# Radial-V_Ext.net
KiCad netlist of a schematic drawn in EAGLE
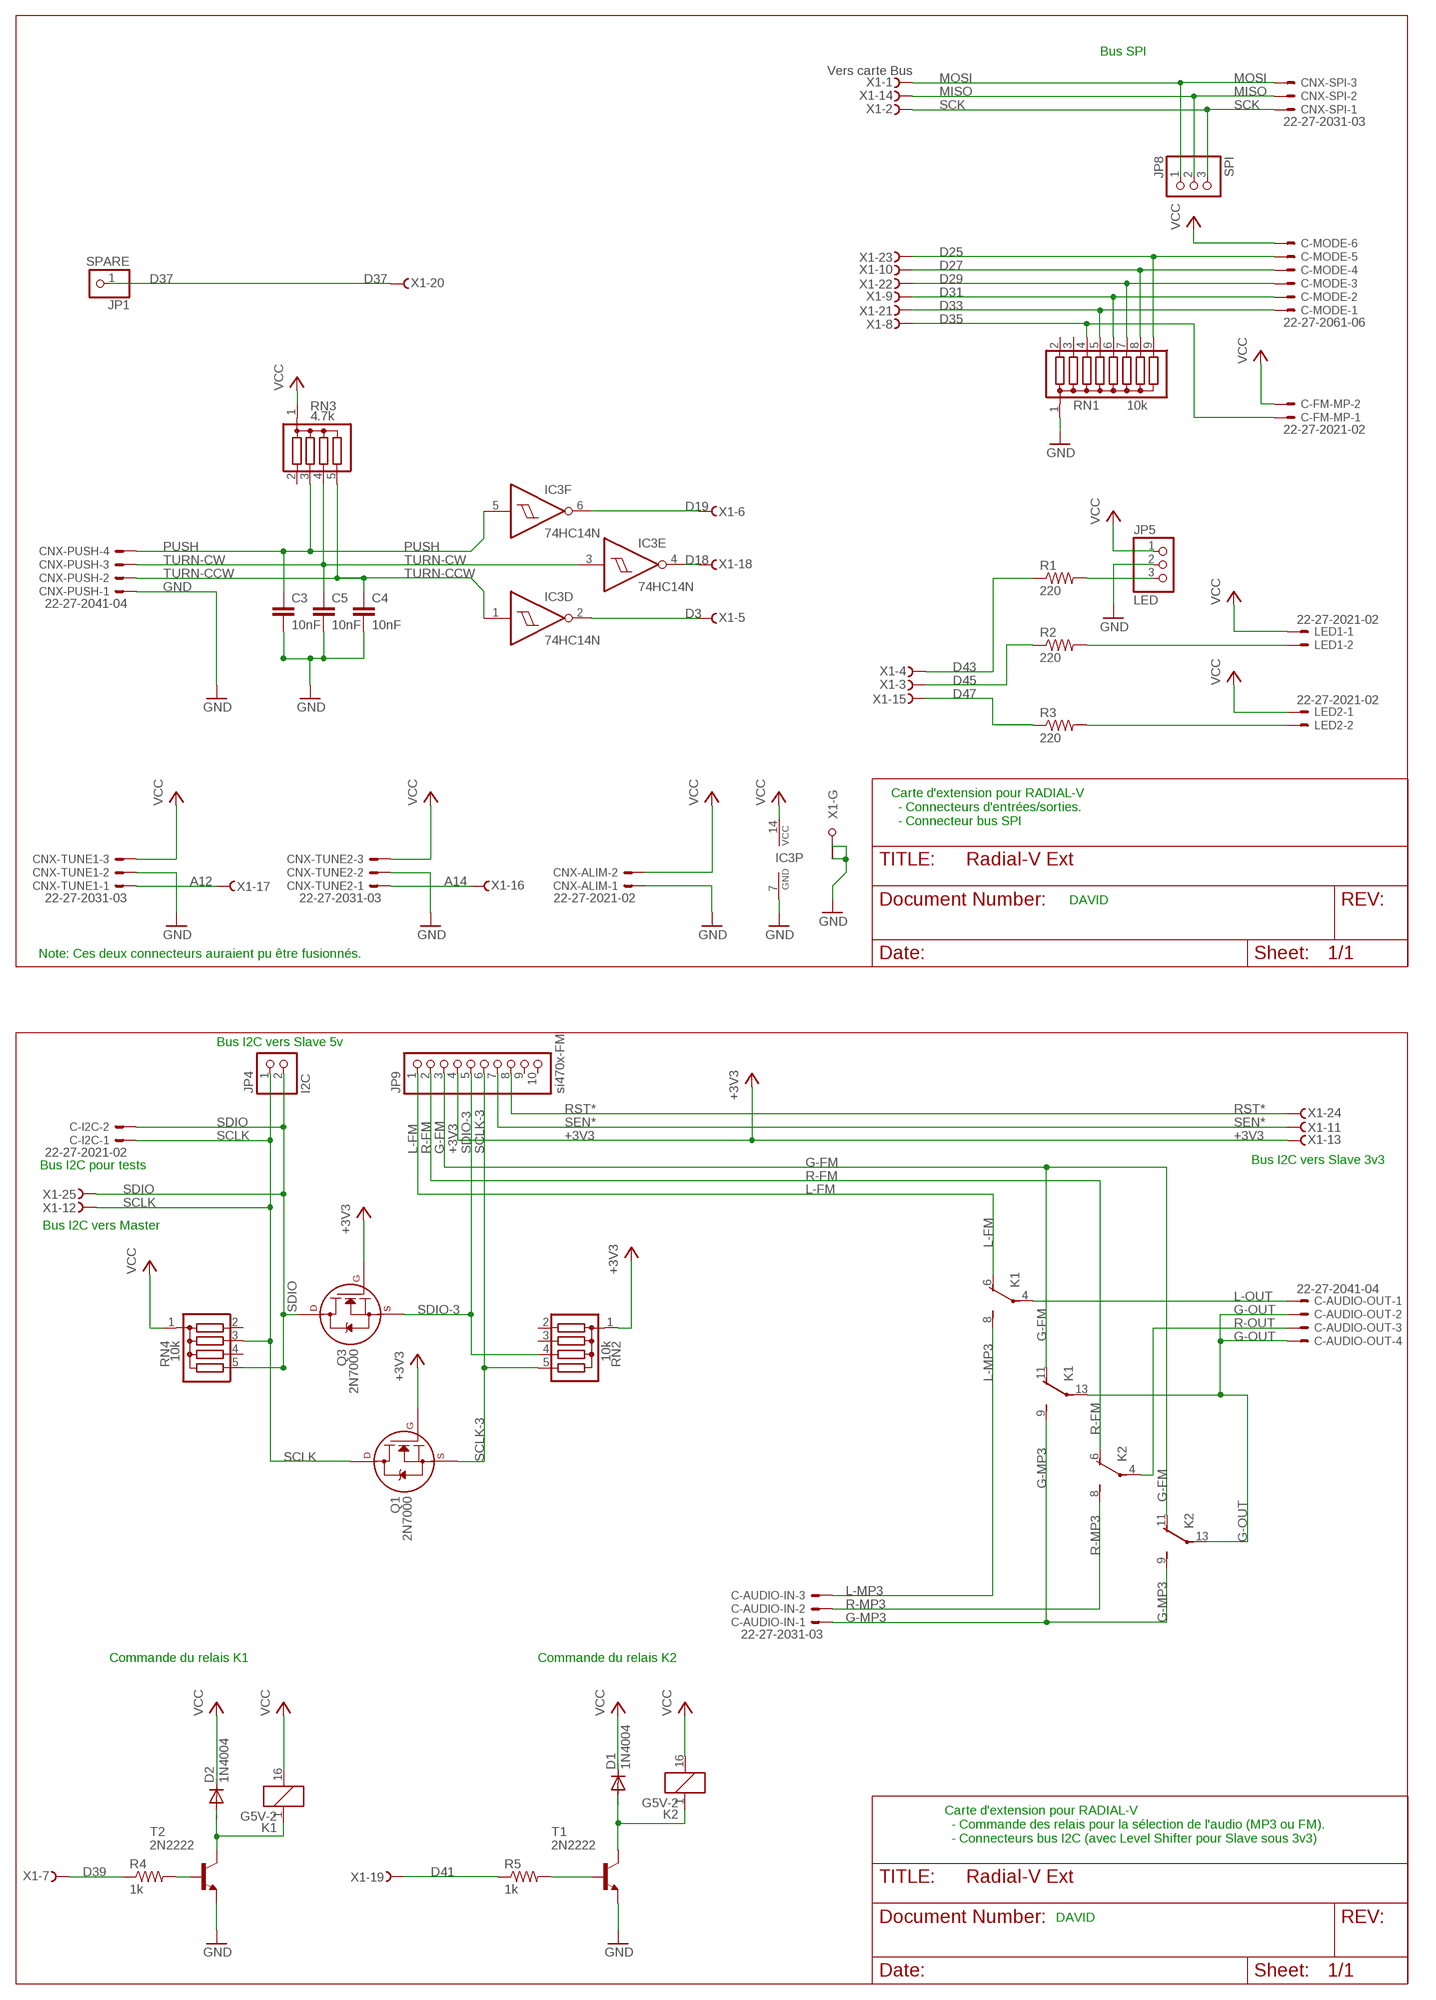
[diagram p0: schematic, sheet 1]

(export (version "E")
  (design (tool "Eeschema 10.0.6"))
  (components
    (comp (ref "C-AUDIO-IN")
      (value "22-27-2031-03")
      (footprint "eagle-import:6410-03")
      (fields (field (name "OC_FARNELL") "2366181"))
      (libsource (lib "eagle-import") (part "22-?-0327-2031"))
    )
    (comp (ref "C-AUDIO-OUT")
      (value "22-27-2041-04")
      (footprint "eagle-import:6410-04")
      (libsource (lib "eagle-import") (part "22-?-0427-2041"))
    )
    (comp (ref "C-FM-MP")
      (value "22-27-2021-02")
      (footprint "eagle-import:6410-02")
      (libsource (lib "eagle-import") (part "22-?-0227-2021"))
    )
    (comp (ref "C-I2C")
      (value "22-27-2021-02")
      (footprint "eagle-import:6410-02")
      (libsource (lib "eagle-import") (part "22-?-0227-2021"))
    )
    (comp (ref "C-MODE")
      (value "22-27-2061-06")
      (footprint "eagle-import:6410-06")
      (libsource (lib "eagle-import") (part "22-?-0627-2061"))
    )
    (comp (ref "C3")
      (value "10nF")
      (footprint "eagle-import:C050-050X075")
      (libsource (lib "eagle-import") (part "C-EU050-050X075"))
    )
    (comp (ref "C4")
      (value "10nF")
      (footprint "eagle-import:C050-050X075")
      (libsource (lib "eagle-import") (part "C-EU050-050X075"))
    )
    (comp (ref "C5")
      (value "10nF")
      (footprint "eagle-import:C050-050X075")
      (libsource (lib "eagle-import") (part "C-EU050-050X075"))
    )
    (comp (ref "CNX-ALIM")
      (value "22-27-2021-02")
      (footprint "eagle-import:6410-02")
      (libsource (lib "eagle-import") (part "22-?-0227-2021"))
    )
    (comp (ref "CNX-PUSH")
      (value "22-27-2041-04")
      (footprint "eagle-import:6410-04")
      (libsource (lib "eagle-import") (part "22-?-0427-2041"))
    )
    (comp (ref "CNX-SPI")
      (value "22-27-2031-03")
      (footprint "eagle-import:6410-03")
      (libsource (lib "eagle-import") (part "22-?-0327-2031"))
    )
    (comp (ref "CNX-TUNE1")
      (value "22-27-2031-03")
      (footprint "eagle-import:6410-03")
      (fields (field (name "OC_FARNELL") "2366181"))
      (libsource (lib "eagle-import") (part "22-?-0327-2031"))
    )
    (comp (ref "CNX-TUNE2")
      (value "22-27-2031-03")
      (footprint "eagle-import:6410-03")
      (fields (field (name "OC_FARNELL") "2366181"))
      (libsource (lib "eagle-import") (part "22-?-0327-2031"))
    )
    (comp (ref "D1")
      (value "1N4004")
      (footprint "eagle-import:DO41-10")
      (libsource (lib "eagle-import") (part "1N4004"))
    )
    (comp (ref "D2")
      (value "1N4004")
      (footprint "eagle-import:DO41-10")
      (libsource (lib "eagle-import") (part "1N4004"))
    )
    (comp (ref "IC3")
      (value "74HC14N")
      (footprint "eagle-import:DIL14")
      (libsource (lib "eagle-import") (part "7414NHC"))
    )
    (comp (ref "JP1")
      (value "SPARE")
      (footprint "eagle-import:1X01")
      (libsource (lib "eagle-import") (part "PINHD-1X1"))
    )
    (comp (ref "JP4")
      (value "I2C")
      (footprint "eagle-import:1X02")
      (libsource (lib "eagle-import") (part "PINHD-1X2"))
    )
    (comp (ref "JP5")
      (value "LED")
      (footprint "eagle-import:1X03")
      (libsource (lib "eagle-import") (part "PINHD-1X3"))
    )
    (comp (ref "JP8")
      (value "SPI")
      (footprint "eagle-import:1X03")
      (libsource (lib "eagle-import") (part "PINHD-1X3"))
    )
    (comp (ref "JP9")
      (value "si470x-FM")
      (footprint "eagle-import:1X10")
      (libsource (lib "eagle-import") (part "PINHD-1X10"))
    )
    (comp (ref "K1")
      (value "G5V-2")
      (footprint "eagle-import:G5V-2")
      (fields (field (name "MPN") "G5V-2 5DC"))
      (libsource (lib "eagle-import") (part "G5V-2"))
    )
    (comp (ref "K2")
      (value "G5V-2")
      (footprint "eagle-import:G5V-2")
      (fields (field (name "MPN") "G5V-2 5DC"))
      (libsource (lib "eagle-import") (part "G5V-2"))
    )
    (comp (ref "LED1")
      (value "22-27-2021-02")
      (footprint "eagle-import:6410-02")
      (libsource (lib "eagle-import") (part "22-?-0227-2021"))
    )
    (comp (ref "LED2")
      (value "22-27-2021-02")
      (footprint "eagle-import:6410-02")
      (libsource (lib "eagle-import") (part "22-?-0227-2021"))
    )
    (comp (ref "Q1")
      (value "2N7000")
      (footprint "eagle-import:TO-92")
      (libsource (lib "eagle-import") (part "2N700_TO920"))
    )
    (comp (ref "Q3")
      (value "2N7000")
      (footprint "eagle-import:TO-92")
      (libsource (lib "eagle-import") (part "2N700_TO920"))
    )
    (comp (ref "R1")
      (value "220")
      (footprint "eagle-import:0411_15")
      (libsource (lib "eagle-import") (part "R-US_0411/15"))
    )
    (comp (ref "R2")
      (value "220")
      (footprint "eagle-import:0411_15")
      (libsource (lib "eagle-import") (part "R-US_0411/15"))
    )
    (comp (ref "R3")
      (value "220")
      (footprint "eagle-import:0411_15")
      (libsource (lib "eagle-import") (part "R-US_0411/15"))
    )
    (comp (ref "R4")
      (value "1k")
      (footprint "eagle-import:0411_15")
      (libsource (lib "eagle-import") (part "R-US_0411/15"))
    )
    (comp (ref "R5")
      (value "1k")
      (footprint "eagle-import:0411_15")
      (libsource (lib "eagle-import") (part "R-US_0411/15"))
    )
    (comp (ref "RN1")
      (value "10k")
      (footprint "eagle-import:SIL9")
      (libsource (lib "eagle-import") (part "G08R"))
    )
    (comp (ref "RN2")
      (value "10k")
      (footprint "eagle-import:SIL5")
      (libsource (lib "eagle-import") (part "G04R"))
    )
    (comp (ref "RN3")
      (value "4.7k")
      (footprint "eagle-import:SIL5")
      (libsource (lib "eagle-import") (part "G04R"))
    )
    (comp (ref "RN4")
      (value "10k")
      (footprint "eagle-import:SIL5")
      (libsource (lib "eagle-import") (part "G04R"))
    )
    (comp (ref "T1")
      (value "2N2222")
      (footprint "eagle-import:TO18")
      (libsource (lib "eagle-import") (part "2N2222"))
    )
    (comp (ref "T2")
      (value "2N2222")
      (footprint "eagle-import:TO18")
      (libsource (lib "eagle-import") (part "2N2222"))
    )
    (comp (ref "X1")
      (value "Vers carte Bus")
      (footprint "eagle-import:F25HP")
      (libsource (lib "eagle-import") (part "F25HPS"))
    )
  )
  (nets
    (net (code "1") (name "+3V3") (class "Default")
      (node (ref "JP9") (pin "4") (pinfunction "4_4") (pintype "passive"))
      (node (ref "Q1") (pin "2") (pinfunction "G_2") (pintype "tri_state"))
      (node (ref "Q3") (pin "2") (pinfunction "G_2") (pintype "tri_state"))
      (node (ref "RN2") (pin "1") (pinfunction "1_1") (pintype "passive"))
      (node (ref "X1") (pin "13") (pinfunction "F_13") (pintype "passive"))
    )
    (net (code "2") (name "/A12") (class "Default")
      (node (ref "CNX-TUNE1") (pin "1") (pinfunction "S_1") (pintype "passive"))
      (node (ref "X1") (pin "17") (pinfunction "F_17") (pintype "passive"))
    )
    (net (code "3") (name "/A14") (class "Default")
      (node (ref "CNX-TUNE2") (pin "1") (pinfunction "S_1") (pintype "passive"))
      (node (ref "X1") (pin "16") (pinfunction "F_16") (pintype "passive"))
    )
    (net (code "4") (name "/D3") (class "Default")
      (node (ref "IC3") (pin "2") (pinfunction "O_2") (pintype "output"))
      (node (ref "X1") (pin "5") (pinfunction "F_5") (pintype "passive"))
    )
    (net (code "5") (name "/D18") (class "Default")
      (node (ref "IC3") (pin "4") (pinfunction "O_4") (pintype "output"))
      (node (ref "X1") (pin "18") (pinfunction "F_18") (pintype "passive"))
    )
    (net (code "6") (name "/D19") (class "Default")
      (node (ref "IC3") (pin "6") (pinfunction "O_6") (pintype "output"))
      (node (ref "X1") (pin "6") (pinfunction "F_6") (pintype "passive"))
    )
    (net (code "7") (name "/D25") (class "Default")
      (node (ref "C-MODE") (pin "5") (pinfunction "S_5") (pintype "passive"))
      (node (ref "RN1") (pin "9") (pinfunction "9_9") (pintype "passive"))
      (node (ref "X1") (pin "23") (pinfunction "F_23") (pintype "passive"))
    )
    (net (code "8") (name "/D27") (class "Default")
      (node (ref "C-MODE") (pin "4") (pinfunction "S_4") (pintype "passive"))
      (node (ref "RN1") (pin "8") (pinfunction "8_8") (pintype "passive"))
      (node (ref "X1") (pin "10") (pinfunction "F_10") (pintype "passive"))
    )
    (net (code "9") (name "/D29") (class "Default")
      (node (ref "C-MODE") (pin "3") (pinfunction "S_3") (pintype "passive"))
      (node (ref "RN1") (pin "7") (pinfunction "7_7") (pintype "passive"))
      (node (ref "X1") (pin "22") (pinfunction "F_22") (pintype "passive"))
    )
    (net (code "10") (name "/D31") (class "Default")
      (node (ref "C-MODE") (pin "2") (pinfunction "S_2") (pintype "passive"))
      (node (ref "RN1") (pin "6") (pinfunction "6_6") (pintype "passive"))
      (node (ref "X1") (pin "9") (pinfunction "F_9") (pintype "passive"))
    )
    (net (code "11") (name "/D33") (class "Default")
      (node (ref "C-MODE") (pin "1") (pinfunction "S_1") (pintype "passive"))
      (node (ref "RN1") (pin "5") (pinfunction "5_5") (pintype "passive"))
      (node (ref "X1") (pin "21") (pinfunction "F_21") (pintype "passive"))
    )
    (net (code "12") (name "/D35") (class "Default")
      (node (ref "C-FM-MP") (pin "1") (pinfunction "S_1") (pintype "passive"))
      (node (ref "RN1") (pin "4") (pinfunction "4_4") (pintype "passive"))
      (node (ref "X1") (pin "8") (pinfunction "F_8") (pintype "passive"))
    )
    (net (code "13") (name "/D37") (class "Default")
      (node (ref "JP1") (pin "1") (pinfunction "1_1") (pintype "passive"))
      (node (ref "X1") (pin "20") (pinfunction "F_20") (pintype "passive"))
    )
    (net (code "14") (name "/D39") (class "Default")
      (node (ref "R4") (pin "1") (pinfunction "1_1") (pintype "passive"))
      (node (ref "X1") (pin "7") (pinfunction "F_7") (pintype "passive"))
    )
    (net (code "15") (name "/D41") (class "Default")
      (node (ref "R5") (pin "1") (pinfunction "1_1") (pintype "passive"))
      (node (ref "X1") (pin "19") (pinfunction "F_19") (pintype "passive"))
    )
    (net (code "16") (name "/D43") (class "Default")
      (node (ref "R1") (pin "1") (pinfunction "1_1") (pintype "passive"))
      (node (ref "X1") (pin "4") (pinfunction "F_4") (pintype "passive"))
    )
    (net (code "17") (name "/D45") (class "Default")
      (node (ref "R2") (pin "1") (pinfunction "1_1") (pintype "passive"))
      (node (ref "X1") (pin "3") (pinfunction "F_3") (pintype "passive"))
    )
    (net (code "18") (name "/D47") (class "Default")
      (node (ref "R3") (pin "1") (pinfunction "1_1") (pintype "passive"))
      (node (ref "X1") (pin "15") (pinfunction "F_15") (pintype "passive"))
    )
    (net (code "19") (name "/G-FM") (class "Default")
      (node (ref "JP9") (pin "3") (pinfunction "3_3") (pintype "passive"))
      (node (ref "K1") (pin "11") (pinfunction "O_11") (pintype "passive"))
      (node (ref "K2") (pin "11") (pinfunction "O_11") (pintype "passive"))
    )
    (net (code "20") (name "/G-MP3") (class "Default")
      (node (ref "C-AUDIO-IN") (pin "1") (pinfunction "S_1") (pintype "passive"))
      (node (ref "K1") (pin "9") (pinfunction "S_9") (pintype "passive"))
      (node (ref "K2") (pin "9") (pinfunction "S_9") (pintype "passive"))
    )
    (net (code "21") (name "/G-OUT") (class "Default")
      (node (ref "C-AUDIO-OUT") (pin "2") (pinfunction "S_2") (pintype "passive"))
      (node (ref "C-AUDIO-OUT") (pin "4") (pinfunction "S_4") (pintype "passive"))
      (node (ref "K1") (pin "13") (pinfunction "P_13") (pintype "passive"))
      (node (ref "K2") (pin "13") (pinfunction "P_13") (pintype "passive"))
    )
    (net (code "22") (name "/L-FM") (class "Default")
      (node (ref "JP9") (pin "1") (pinfunction "1_1") (pintype "passive"))
      (node (ref "K1") (pin "6") (pinfunction "O_6") (pintype "passive"))
    )
    (net (code "23") (name "/L-MP3") (class "Default")
      (node (ref "C-AUDIO-IN") (pin "3") (pinfunction "S_3") (pintype "passive"))
      (node (ref "K1") (pin "8") (pinfunction "S_8") (pintype "passive"))
    )
    (net (code "24") (name "/L-OUT") (class "Default")
      (node (ref "C-AUDIO-OUT") (pin "1") (pinfunction "S_1") (pintype "passive"))
      (node (ref "K1") (pin "4") (pinfunction "P_4") (pintype "passive"))
    )
    (net (code "25") (name "/MISO") (class "Default")
      (node (ref "CNX-SPI") (pin "2") (pinfunction "S_2") (pintype "passive"))
      (node (ref "JP8") (pin "2") (pinfunction "2_2") (pintype "passive"))
      (node (ref "X1") (pin "14") (pinfunction "F_14") (pintype "passive"))
    )
    (net (code "26") (name "/MOSI") (class "Default")
      (node (ref "CNX-SPI") (pin "3") (pinfunction "S_3") (pintype "passive"))
      (node (ref "JP8") (pin "1") (pinfunction "1_1") (pintype "passive"))
      (node (ref "X1") (pin "1") (pinfunction "F_1") (pintype "passive"))
    )
    (net (code "27") (name "/PUSH") (class "Default")
      (node (ref "C3") (pin "1") (pinfunction "1_1") (pintype "passive"))
      (node (ref "CNX-PUSH") (pin "4") (pinfunction "S_4") (pintype "passive"))
      (node (ref "IC3") (pin "5") (pinfunction "I_5") (pintype "input"))
      (node (ref "RN3") (pin "3") (pinfunction "3_3") (pintype "passive"))
    )
    (net (code "28") (name "/R-FM") (class "Default")
      (node (ref "JP9") (pin "2") (pinfunction "2_2") (pintype "passive"))
      (node (ref "K2") (pin "6") (pinfunction "O_6") (pintype "passive"))
    )
    (net (code "29") (name "/R-MP3") (class "Default")
      (node (ref "C-AUDIO-IN") (pin "2") (pinfunction "S_2") (pintype "passive"))
      (node (ref "K2") (pin "8") (pinfunction "S_8") (pintype "passive"))
    )
    (net (code "30") (name "/R-OUT") (class "Default")
      (node (ref "C-AUDIO-OUT") (pin "3") (pinfunction "S_3") (pintype "passive"))
      (node (ref "K2") (pin "4") (pinfunction "P_4") (pintype "passive"))
    )
    (net (code "31") (name "/RST*") (class "Default")
      (node (ref "JP9") (pin "8") (pinfunction "8_8") (pintype "passive"))
      (node (ref "X1") (pin "24") (pinfunction "F_24") (pintype "passive"))
    )
    (net (code "32") (name "/SCK") (class "Default")
      (node (ref "CNX-SPI") (pin "1") (pinfunction "S_1") (pintype "passive"))
      (node (ref "JP8") (pin "3") (pinfunction "3_3") (pintype "passive"))
      (node (ref "X1") (pin "2") (pinfunction "F_2") (pintype "passive"))
    )
    (net (code "33") (name "/SCLK") (class "Default")
      (node (ref "C-I2C") (pin "1") (pinfunction "S_1") (pintype "passive"))
      (node (ref "JP4") (pin "1") (pinfunction "1_1") (pintype "passive"))
      (node (ref "Q1") (pin "3") (pinfunction "D_3") (pintype "bidirectional"))
      (node (ref "RN4") (pin "3") (pinfunction "3_3") (pintype "passive"))
      (node (ref "X1") (pin "12") (pinfunction "F_12") (pintype "passive"))
    )
    (net (code "34") (name "/SCLK-3") (class "Default")
      (node (ref "JP9") (pin "6") (pinfunction "6_6") (pintype "passive"))
      (node (ref "Q1") (pin "1") (pinfunction "S_1") (pintype "bidirectional"))
      (node (ref "RN2") (pin "5") (pinfunction "5_5") (pintype "passive"))
    )
    (net (code "35") (name "/SDIO") (class "Default")
      (node (ref "C-I2C") (pin "2") (pinfunction "S_2") (pintype "passive"))
      (node (ref "JP4") (pin "2") (pinfunction "2_2") (pintype "passive"))
      (node (ref "Q3") (pin "3") (pinfunction "D_3") (pintype "bidirectional"))
      (node (ref "RN4") (pin "5") (pinfunction "5_5") (pintype "passive"))
      (node (ref "X1") (pin "25") (pinfunction "F_25") (pintype "passive"))
    )
    (net (code "36") (name "/SDIO-3") (class "Default")
      (node (ref "JP9") (pin "5") (pinfunction "5_5") (pintype "passive"))
      (node (ref "Q3") (pin "1") (pinfunction "S_1") (pintype "bidirectional"))
      (node (ref "RN2") (pin "4") (pinfunction "4_4") (pintype "passive"))
    )
    (net (code "37") (name "/SEN*") (class "Default")
      (node (ref "JP9") (pin "7") (pinfunction "7_7") (pintype "passive"))
      (node (ref "X1") (pin "11") (pinfunction "F_11") (pintype "passive"))
    )
    (net (code "38") (name "/TURN-CCW") (class "Default")
      (node (ref "C4") (pin "1") (pinfunction "1_1") (pintype "passive"))
      (node (ref "CNX-PUSH") (pin "2") (pinfunction "S_2") (pintype "passive"))
      (node (ref "IC3") (pin "1") (pinfunction "I_1") (pintype "input"))
      (node (ref "RN3") (pin "5") (pinfunction "5_5") (pintype "passive"))
    )
    (net (code "39") (name "/TURN-CW") (class "Default")
      (node (ref "C5") (pin "1") (pinfunction "1_1") (pintype "passive"))
      (node (ref "CNX-PUSH") (pin "3") (pinfunction "S_3") (pintype "passive"))
      (node (ref "IC3") (pin "3") (pinfunction "I_3") (pintype "input"))
      (node (ref "RN3") (pin "4") (pinfunction "4_4") (pintype "passive"))
    )
    (net (code "40") (name "GND") (class "Default")
      (node (ref "C3") (pin "2") (pinfunction "2_2") (pintype "passive"))
      (node (ref "C4") (pin "2") (pinfunction "2_2") (pintype "passive"))
      (node (ref "C5") (pin "2") (pinfunction "2_2") (pintype "passive"))
      (node (ref "CNX-ALIM") (pin "1") (pinfunction "S_1") (pintype "passive"))
      (node (ref "CNX-PUSH") (pin "1") (pinfunction "S_1") (pintype "passive"))
      (node (ref "CNX-TUNE1") (pin "2") (pinfunction "S_2") (pintype "passive"))
      (node (ref "CNX-TUNE2") (pin "2") (pinfunction "S_2") (pintype "passive"))
      (node (ref "IC3") (pin "7") (pinfunction "GND_7") (pintype "power_in"))
      (node (ref "JP5") (pin "2") (pinfunction "2_2") (pintype "passive"))
      (node (ref "RN1") (pin "1") (pinfunction "1_1") (pintype "passive"))
      (node (ref "T1") (pin "1") (pinfunction "E_1") (pintype "passive"))
      (node (ref "T2") (pin "1") (pinfunction "E_1") (pintype "passive"))
      (node (ref "X1") (pin "G1") (pinfunction "G1_G1") (pintype "passive"))
      (node (ref "X1") (pin "G2") (pinfunction "G2_G2") (pintype "passive"))
    )
    (net (code "41") (name "Net-(JP5-Pad3)") (class "Default")
      (node (ref "JP5") (pin "3") (pinfunction "3_3") (pintype "passive"))
      (node (ref "R1") (pin "2") (pinfunction "2_2") (pintype "passive"))
    )
    (net (code "42") (name "Net-(LED1B-S)") (class "Default")
      (node (ref "LED1") (pin "2") (pinfunction "S_2") (pintype "passive"))
      (node (ref "R2") (pin "2") (pinfunction "2_2") (pintype "passive"))
    )
    (net (code "43") (name "Net-(LED2B-S)") (class "Default")
      (node (ref "LED2") (pin "2") (pinfunction "S_2") (pintype "passive"))
      (node (ref "R3") (pin "2") (pinfunction "2_2") (pintype "passive"))
    )
    (net (code "44") (name "Net-(T1-B)") (class "Default")
      (node (ref "R5") (pin "2") (pinfunction "2_2") (pintype "passive"))
      (node (ref "T1") (pin "2") (pinfunction "B_2") (pintype "passive"))
    )
    (net (code "45") (name "Net-(T1-C)") (class "Default")
      (node (ref "D1") (pin "A") (pinfunction "A_A") (pintype "passive"))
      (node (ref "K2") (pin "1") (pinfunction "1_1") (pintype "passive"))
      (node (ref "T1") (pin "3") (pinfunction "C_3") (pintype "passive"))
    )
    (net (code "46") (name "Net-(T2-B)") (class "Default")
      (node (ref "R4") (pin "2") (pinfunction "2_2") (pintype "passive"))
      (node (ref "T2") (pin "2") (pinfunction "B_2") (pintype "passive"))
    )
    (net (code "47") (name "Net-(T2-C)") (class "Default")
      (node (ref "D2") (pin "A") (pinfunction "A_A") (pintype "passive"))
      (node (ref "K1") (pin "1") (pinfunction "1_1") (pintype "passive"))
      (node (ref "T2") (pin "3") (pinfunction "C_3") (pintype "passive"))
    )
    (net (code "48") (name "VCC") (class "Default")
      (node (ref "C-FM-MP") (pin "2") (pinfunction "S_2") (pintype "passive"))
      (node (ref "C-MODE") (pin "6") (pinfunction "S_6") (pintype "passive"))
      (node (ref "CNX-ALIM") (pin "2") (pinfunction "S_2") (pintype "passive"))
      (node (ref "CNX-TUNE1") (pin "3") (pinfunction "S_3") (pintype "passive"))
      (node (ref "CNX-TUNE2") (pin "3") (pinfunction "S_3") (pintype "passive"))
      (node (ref "D1") (pin "C") (pinfunction "C_C") (pintype "passive"))
      (node (ref "D2") (pin "C") (pinfunction "C_C") (pintype "passive"))
      (node (ref "IC3") (pin "14") (pinfunction "VCC_14") (pintype "power_in"))
      (node (ref "JP5") (pin "1") (pinfunction "1_1") (pintype "passive"))
      (node (ref "K1") (pin "16") (pinfunction "2_16") (pintype "passive"))
      (node (ref "K2") (pin "16") (pinfunction "2_16") (pintype "passive"))
      (node (ref "LED1") (pin "1") (pinfunction "S_1") (pintype "passive"))
      (node (ref "LED2") (pin "1") (pinfunction "S_1") (pintype "passive"))
      (node (ref "RN3") (pin "1") (pinfunction "1_1") (pintype "passive"))
      (node (ref "RN4") (pin "1") (pinfunction "1_1") (pintype "passive"))
    )
    (net (code "49") (name "unconnected-(JP9-Pad9)") (class "Default")
      (node (ref "JP9") (pin "9") (pinfunction "9_9") (pintype "passive"))
    )
    (net (code "50") (name "unconnected-(JP9-Pad10)") (class "Default")
      (node (ref "JP9") (pin "10") (pinfunction "10_10") (pintype "passive"))
    )
    (net (code "51") (name "unconnected-(RN1-Pad2)") (class "Default")
      (node (ref "RN1") (pin "2") (pinfunction "2_2") (pintype "passive"))
    )
    (net (code "52") (name "unconnected-(RN1-Pad3)") (class "Default")
      (node (ref "RN1") (pin "3") (pinfunction "3_3") (pintype "passive"))
    )
    (net (code "53") (name "unconnected-(RN2-Pad2)") (class "Default")
      (node (ref "RN2") (pin "2") (pinfunction "2_2") (pintype "passive"))
    )
    (net (code "54") (name "unconnected-(RN2-Pad3)") (class "Default")
      (node (ref "RN2") (pin "3") (pinfunction "3_3") (pintype "passive"))
    )
    (net (code "55") (name "unconnected-(RN3-Pad2)") (class "Default")
      (node (ref "RN3") (pin "2") (pinfunction "2_2") (pintype "passive"))
    )
    (net (code "56") (name "unconnected-(RN4-Pad2)") (class "Default")
      (node (ref "RN4") (pin "2") (pinfunction "2_2") (pintype "passive"))
    )
    (net (code "57") (name "unconnected-(RN4-Pad4)") (class "Default")
      (node (ref "RN4") (pin "4") (pinfunction "4_4") (pintype "passive"))
    )
  )
)
